# Yet-Another-LED-Cube.net
KiCad netlist of a schematic drawn in EAGLE
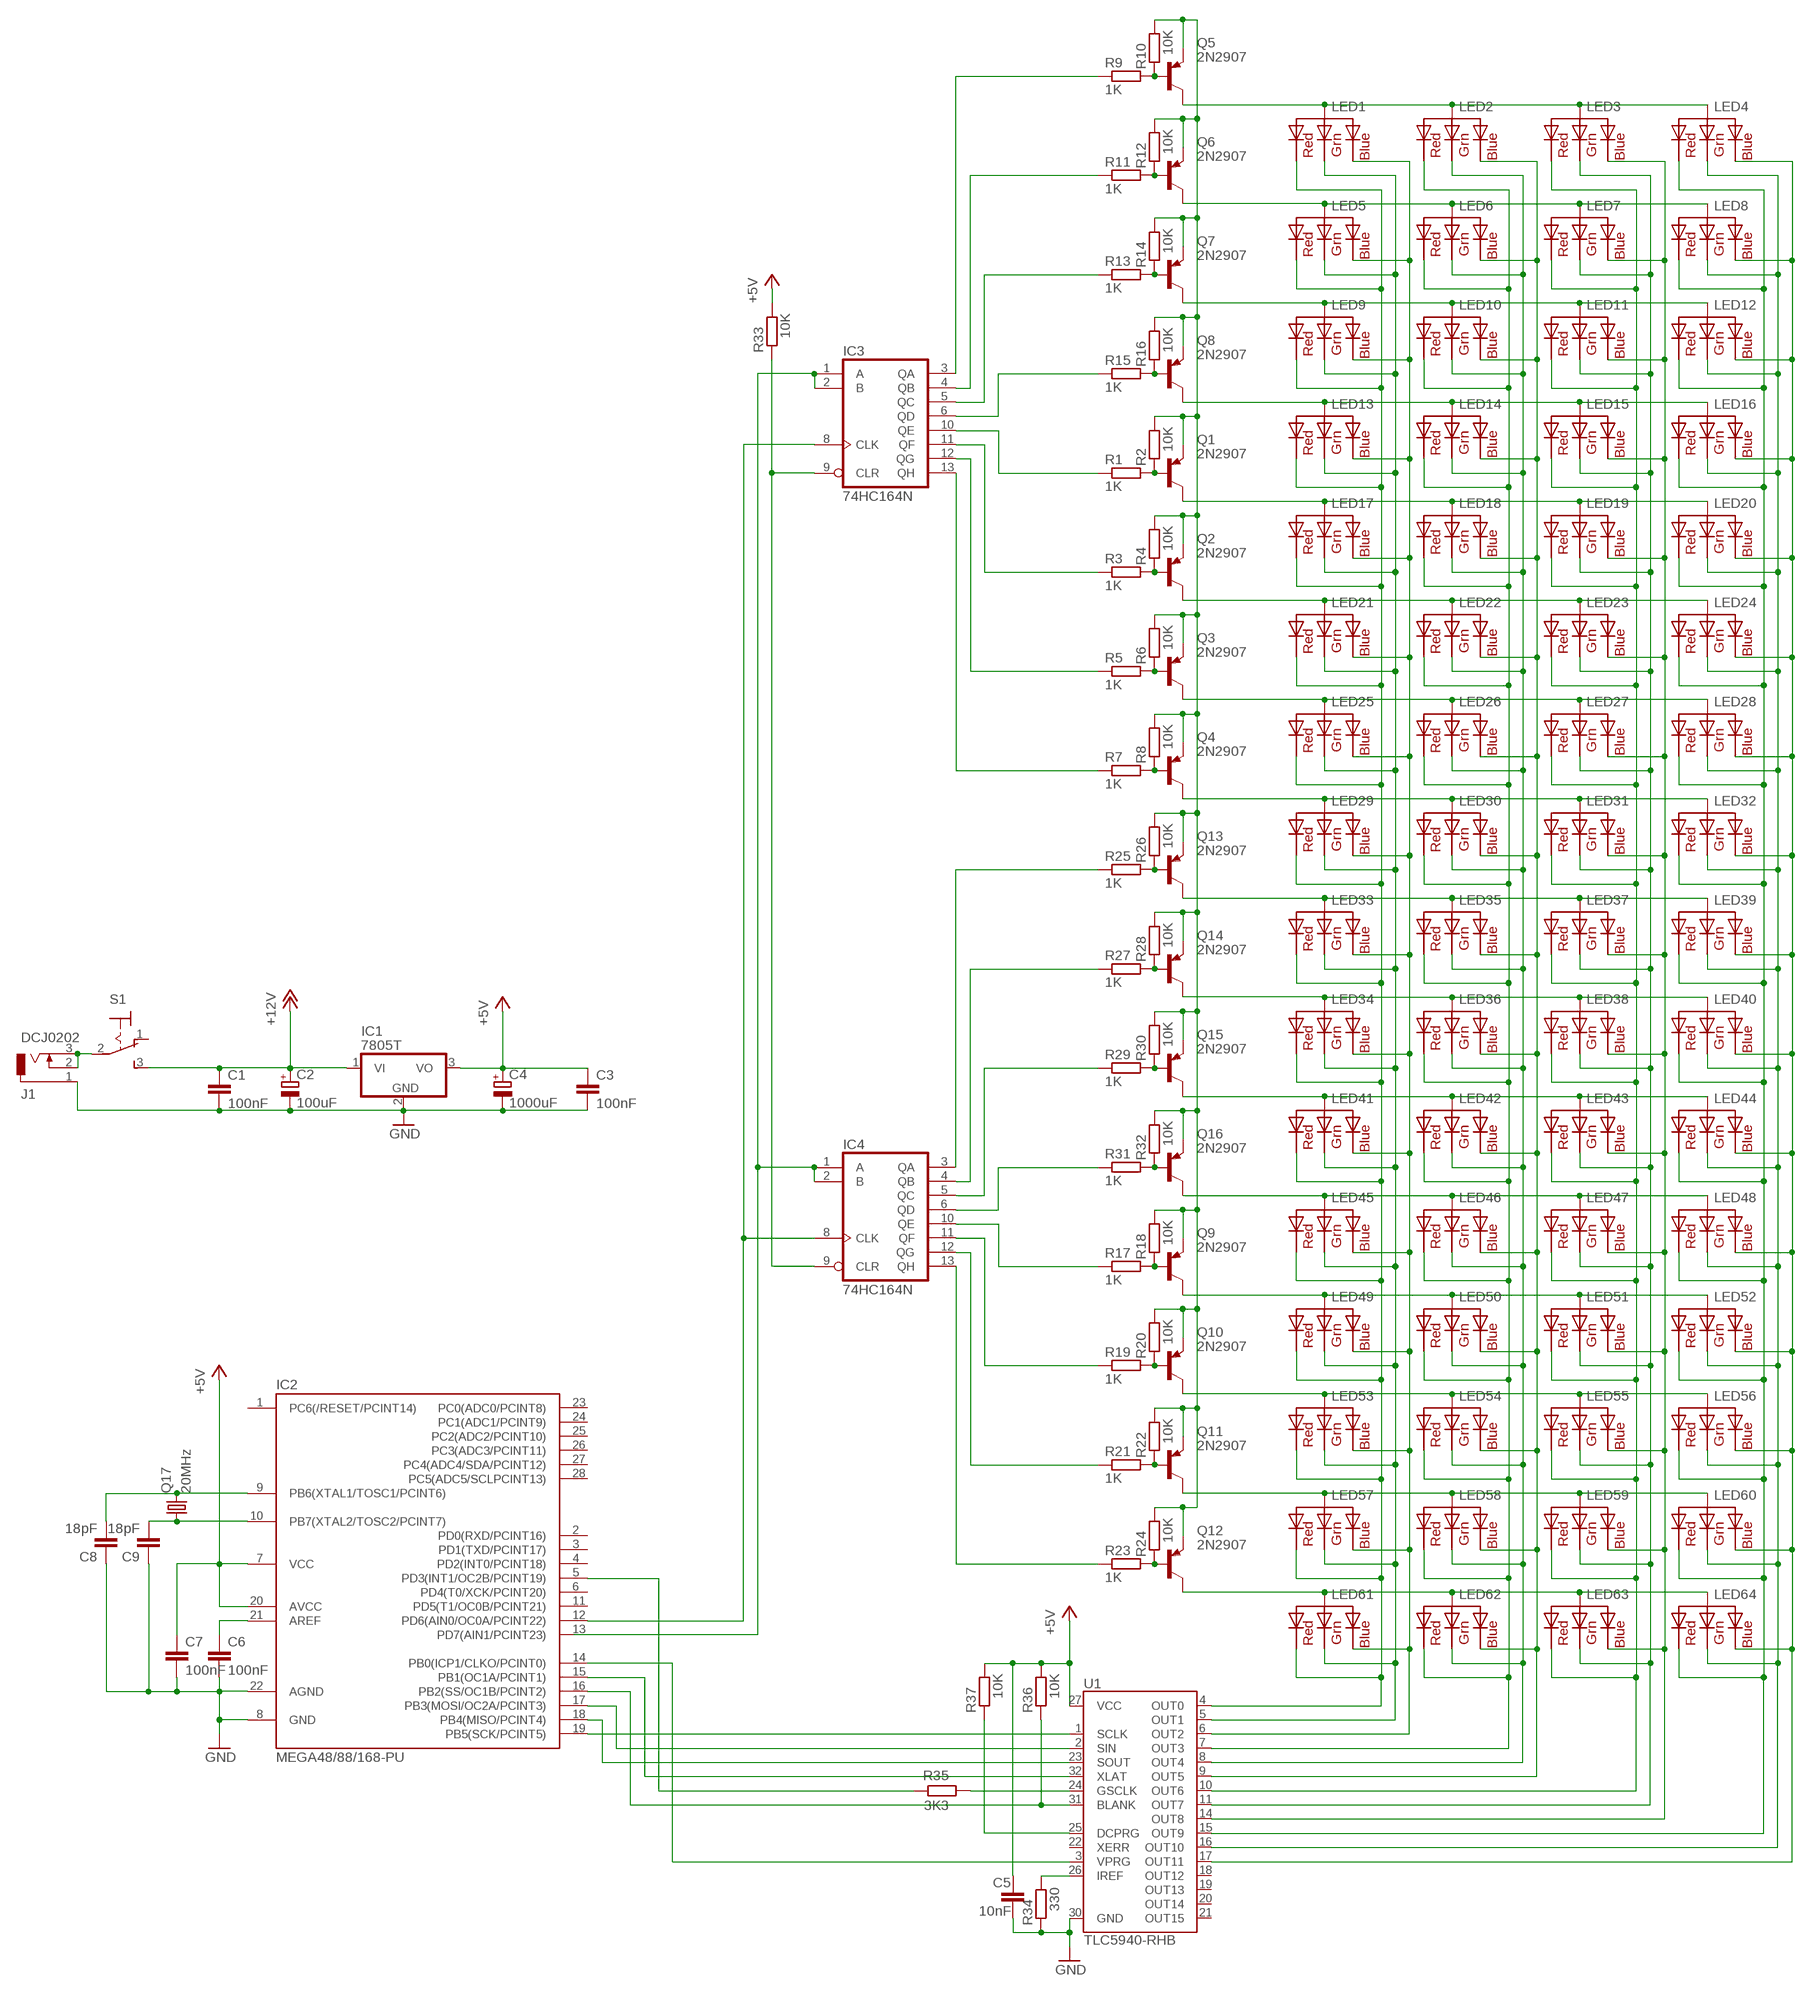
[diagram p0: schematic, sheet 1]

(export (version "E")
  (design (tool "Eeschema 10.0.6"))
  (components
    (comp (ref "C1")
      (value "100nF")
      (footprint "eagle-import:C025-024X044")
      (libsource (lib "eagle-import") (part "C-EU025-024X044"))
    )
    (comp (ref "C2")
      (value "100uF")
      (footprint "eagle-import:E2,5-7")
      (libsource (lib "eagle-import") (part "CPOL-EUE2.5-7"))
    )
    (comp (ref "C3")
      (value "100nF")
      (footprint "eagle-import:C025-024X044")
      (libsource (lib "eagle-import") (part "C-EU025-024X044"))
    )
    (comp (ref "C4")
      (value "1000uF")
      (footprint "eagle-import:E3,5-10")
      (libsource (lib "eagle-import") (part "CPOL-EUE3.5-10"))
    )
    (comp (ref "C5")
      (value "10nF")
      (footprint "eagle-import:C025-024X044")
      (libsource (lib "eagle-import") (part "C-EU025-024X044"))
    )
    (comp (ref "C6")
      (value "100nF")
      (footprint "eagle-import:C025-024X044")
      (libsource (lib "eagle-import") (part "C-EU025-024X044"))
    )
    (comp (ref "C7")
      (value "100nF")
      (footprint "eagle-import:C025-024X044")
      (libsource (lib "eagle-import") (part "C-EU025-024X044"))
    )
    (comp (ref "C8")
      (value "18pF")
      (footprint "eagle-import:C025-024X044")
      (libsource (lib "eagle-import") (part "C-EU025-024X044"))
    )
    (comp (ref "C9")
      (value "18pF")
      (footprint "eagle-import:C025-024X044")
      (libsource (lib "eagle-import") (part "C-EU025-024X044"))
    )
    (comp (ref "IC1")
      (value "7805T")
      (footprint "eagle-import:TO220H")
      (libsource (lib "eagle-import") (part "78T05"))
    )
    (comp (ref "IC2")
      (value "MEGA48/88/168-PU")
      (footprint "eagle-import:DIL28-3")
      (libsource (lib "eagle-import") (part "MEGA48/88/168-PU"))
    )
    (comp (ref "IC3")
      (value "74HC164N")
      (footprint "eagle-import:DIL14")
      (libsource (lib "eagle-import") (part "74164NHC"))
    )
    (comp (ref "IC4")
      (value "74HC164N")
      (footprint "eagle-import:DIL14")
      (libsource (lib "eagle-import") (part "74164NHC"))
    )
    (comp (ref "J1")
      (value "DCJ0202")
      (footprint "eagle-import:DCJ0202")
      (libsource (lib "eagle-import") (part "DCJ0202"))
    )
    (comp (ref "LED1")
      (value "RGBLED_CAA")
      (footprint "eagle-import:LED5MMRGB2")
      (libsource (lib "eagle-import") (part "RGBLED_CAA"))
    )
    (comp (ref "LED2")
      (value "RGBLED_CAA")
      (footprint "eagle-import:LED5MMRGB2")
      (libsource (lib "eagle-import") (part "RGBLED_CAA"))
    )
    (comp (ref "LED3")
      (value "RGBLED_CAA")
      (footprint "eagle-import:LED5MMRGB2")
      (libsource (lib "eagle-import") (part "RGBLED_CAA"))
    )
    (comp (ref "LED4")
      (value "RGBLED_CAA")
      (footprint "eagle-import:LED5MMRGB2")
      (libsource (lib "eagle-import") (part "RGBLED_CAA"))
    )
    (comp (ref "LED5")
      (value "RGBLED_CAA")
      (footprint "eagle-import:LED5MMRGB2")
      (libsource (lib "eagle-import") (part "RGBLED_CAA"))
    )
    (comp (ref "LED6")
      (value "RGBLED_CAA")
      (footprint "eagle-import:LED5MMRGB2")
      (libsource (lib "eagle-import") (part "RGBLED_CAA"))
    )
    (comp (ref "LED7")
      (value "RGBLED_CAA")
      (footprint "eagle-import:LED5MMRGB2")
      (libsource (lib "eagle-import") (part "RGBLED_CAA"))
    )
    (comp (ref "LED8")
      (value "RGBLED_CAA")
      (footprint "eagle-import:LED5MMRGB2")
      (libsource (lib "eagle-import") (part "RGBLED_CAA"))
    )
    (comp (ref "LED9")
      (value "RGBLED_CAA")
      (footprint "eagle-import:LED5MMRGB2")
      (libsource (lib "eagle-import") (part "RGBLED_CAA"))
    )
    (comp (ref "LED10")
      (value "RGBLED_CAA")
      (footprint "eagle-import:LED5MMRGB2")
      (libsource (lib "eagle-import") (part "RGBLED_CAA"))
    )
    (comp (ref "LED11")
      (value "RGBLED_CAA")
      (footprint "eagle-import:LED5MMRGB2")
      (libsource (lib "eagle-import") (part "RGBLED_CAA"))
    )
    (comp (ref "LED12")
      (value "RGBLED_CAA")
      (footprint "eagle-import:LED5MMRGB2")
      (libsource (lib "eagle-import") (part "RGBLED_CAA"))
    )
    (comp (ref "LED13")
      (value "RGBLED_CAA")
      (footprint "eagle-import:LED5MMRGB2")
      (libsource (lib "eagle-import") (part "RGBLED_CAA"))
    )
    (comp (ref "LED14")
      (value "RGBLED_CAA")
      (footprint "eagle-import:LED5MMRGB2")
      (libsource (lib "eagle-import") (part "RGBLED_CAA"))
    )
    (comp (ref "LED15")
      (value "RGBLED_CAA")
      (footprint "eagle-import:LED5MMRGB2")
      (libsource (lib "eagle-import") (part "RGBLED_CAA"))
    )
    (comp (ref "LED16")
      (value "RGBLED_CAA")
      (footprint "eagle-import:LED5MMRGB2")
      (libsource (lib "eagle-import") (part "RGBLED_CAA"))
    )
    (comp (ref "LED17")
      (value "RGBLED_CAA")
      (footprint "eagle-import:LED5MMRGB2")
      (libsource (lib "eagle-import") (part "RGBLED_CAA"))
    )
    (comp (ref "LED18")
      (value "RGBLED_CAA")
      (footprint "eagle-import:LED5MMRGB2")
      (libsource (lib "eagle-import") (part "RGBLED_CAA"))
    )
    (comp (ref "LED19")
      (value "RGBLED_CAA")
      (footprint "eagle-import:LED5MMRGB2")
      (libsource (lib "eagle-import") (part "RGBLED_CAA"))
    )
    (comp (ref "LED20")
      (value "RGBLED_CAA")
      (footprint "eagle-import:LED5MMRGB2")
      (libsource (lib "eagle-import") (part "RGBLED_CAA"))
    )
    (comp (ref "LED21")
      (value "RGBLED_CAA")
      (footprint "eagle-import:LED5MMRGB2")
      (libsource (lib "eagle-import") (part "RGBLED_CAA"))
    )
    (comp (ref "LED22")
      (value "RGBLED_CAA")
      (footprint "eagle-import:LED5MMRGB2")
      (libsource (lib "eagle-import") (part "RGBLED_CAA"))
    )
    (comp (ref "LED23")
      (value "RGBLED_CAA")
      (footprint "eagle-import:LED5MMRGB2")
      (libsource (lib "eagle-import") (part "RGBLED_CAA"))
    )
    (comp (ref "LED24")
      (value "RGBLED_CAA")
      (footprint "eagle-import:LED5MMRGB2")
      (libsource (lib "eagle-import") (part "RGBLED_CAA"))
    )
    (comp (ref "LED25")
      (value "RGBLED_CAA")
      (footprint "eagle-import:LED5MMRGB2")
      (libsource (lib "eagle-import") (part "RGBLED_CAA"))
    )
    (comp (ref "LED26")
      (value "RGBLED_CAA")
      (footprint "eagle-import:LED5MMRGB2")
      (libsource (lib "eagle-import") (part "RGBLED_CAA"))
    )
    (comp (ref "LED27")
      (value "RGBLED_CAA")
      (footprint "eagle-import:LED5MMRGB2")
      (libsource (lib "eagle-import") (part "RGBLED_CAA"))
    )
    (comp (ref "LED28")
      (value "RGBLED_CAA")
      (footprint "eagle-import:LED5MMRGB2")
      (libsource (lib "eagle-import") (part "RGBLED_CAA"))
    )
    (comp (ref "LED29")
      (value "RGBLED_CAA")
      (footprint "eagle-import:LED5MMRGB2")
      (libsource (lib "eagle-import") (part "RGBLED_CAA"))
    )
    (comp (ref "LED30")
      (value "RGBLED_CAA")
      (footprint "eagle-import:LED5MMRGB2")
      (libsource (lib "eagle-import") (part "RGBLED_CAA"))
    )
    (comp (ref "LED31")
      (value "RGBLED_CAA")
      (footprint "eagle-import:LED5MMRGB2")
      (libsource (lib "eagle-import") (part "RGBLED_CAA"))
    )
    (comp (ref "LED32")
      (value "RGBLED_CAA")
      (footprint "eagle-import:LED5MMRGB2")
      (libsource (lib "eagle-import") (part "RGBLED_CAA"))
    )
    (comp (ref "LED33")
      (value "RGBLED_CAA")
      (footprint "eagle-import:LED5MMRGB2")
      (libsource (lib "eagle-import") (part "RGBLED_CAA"))
    )
    (comp (ref "LED34")
      (value "RGBLED_CAA")
      (footprint "eagle-import:LED5MMRGB2")
      (libsource (lib "eagle-import") (part "RGBLED_CAA"))
    )
    (comp (ref "LED35")
      (value "RGBLED_CAA")
      (footprint "eagle-import:LED5MMRGB2")
      (libsource (lib "eagle-import") (part "RGBLED_CAA"))
    )
    (comp (ref "LED36")
      (value "RGBLED_CAA")
      (footprint "eagle-import:LED5MMRGB2")
      (libsource (lib "eagle-import") (part "RGBLED_CAA"))
    )
    (comp (ref "LED37")
      (value "RGBLED_CAA")
      (footprint "eagle-import:LED5MMRGB2")
      (libsource (lib "eagle-import") (part "RGBLED_CAA"))
    )
    (comp (ref "LED38")
      (value "RGBLED_CAA")
      (footprint "eagle-import:LED5MMRGB2")
      (libsource (lib "eagle-import") (part "RGBLED_CAA"))
    )
    (comp (ref "LED39")
      (value "RGBLED_CAA")
      (footprint "eagle-import:LED5MMRGB2")
      (libsource (lib "eagle-import") (part "RGBLED_CAA"))
    )
    (comp (ref "LED40")
      (value "RGBLED_CAA")
      (footprint "eagle-import:LED5MMRGB2")
      (libsource (lib "eagle-import") (part "RGBLED_CAA"))
    )
    (comp (ref "LED41")
      (value "RGBLED_CAA")
      (footprint "eagle-import:LED5MMRGB2")
      (libsource (lib "eagle-import") (part "RGBLED_CAA"))
    )
    (comp (ref "LED42")
      (value "RGBLED_CAA")
      (footprint "eagle-import:LED5MMRGB2")
      (libsource (lib "eagle-import") (part "RGBLED_CAA"))
    )
    (comp (ref "LED43")
      (value "RGBLED_CAA")
      (footprint "eagle-import:LED5MMRGB2")
      (libsource (lib "eagle-import") (part "RGBLED_CAA"))
    )
    (comp (ref "LED44")
      (value "RGBLED_CAA")
      (footprint "eagle-import:LED5MMRGB2")
      (libsource (lib "eagle-import") (part "RGBLED_CAA"))
    )
    (comp (ref "LED45")
      (value "RGBLED_CAA")
      (footprint "eagle-import:LED5MMRGB2")
      (libsource (lib "eagle-import") (part "RGBLED_CAA"))
    )
    (comp (ref "LED46")
      (value "RGBLED_CAA")
      (footprint "eagle-import:LED5MMRGB2")
      (libsource (lib "eagle-import") (part "RGBLED_CAA"))
    )
    (comp (ref "LED47")
      (value "RGBLED_CAA")
      (footprint "eagle-import:LED5MMRGB2")
      (libsource (lib "eagle-import") (part "RGBLED_CAA"))
    )
    (comp (ref "LED48")
      (value "RGBLED_CAA")
      (footprint "eagle-import:LED5MMRGB2")
      (libsource (lib "eagle-import") (part "RGBLED_CAA"))
    )
    (comp (ref "LED49")
      (value "RGBLED_CAA")
      (footprint "eagle-import:LED5MMRGB2")
      (libsource (lib "eagle-import") (part "RGBLED_CAA"))
    )
    (comp (ref "LED50")
      (value "RGBLED_CAA")
      (footprint "eagle-import:LED5MMRGB2")
      (libsource (lib "eagle-import") (part "RGBLED_CAA"))
    )
    (comp (ref "LED51")
      (value "RGBLED_CAA")
      (footprint "eagle-import:LED5MMRGB2")
      (libsource (lib "eagle-import") (part "RGBLED_CAA"))
    )
    (comp (ref "LED52")
      (value "RGBLED_CAA")
      (footprint "eagle-import:LED5MMRGB2")
      (libsource (lib "eagle-import") (part "RGBLED_CAA"))
    )
    (comp (ref "LED53")
      (value "RGBLED_CAA")
      (footprint "eagle-import:LED5MMRGB2")
      (libsource (lib "eagle-import") (part "RGBLED_CAA"))
    )
    (comp (ref "LED54")
      (value "RGBLED_CAA")
      (footprint "eagle-import:LED5MMRGB2")
      (libsource (lib "eagle-import") (part "RGBLED_CAA"))
    )
    (comp (ref "LED55")
      (value "RGBLED_CAA")
      (footprint "eagle-import:LED5MMRGB2")
      (libsource (lib "eagle-import") (part "RGBLED_CAA"))
    )
    (comp (ref "LED56")
      (value "RGBLED_CAA")
      (footprint "eagle-import:LED5MMRGB2")
      (libsource (lib "eagle-import") (part "RGBLED_CAA"))
    )
    (comp (ref "LED57")
      (value "RGBLED_CAA")
      (footprint "eagle-import:LED5MMRGB2")
      (libsource (lib "eagle-import") (part "RGBLED_CAA"))
    )
    (comp (ref "LED58")
      (value "RGBLED_CAA")
      (footprint "eagle-import:LED5MMRGB2")
      (libsource (lib "eagle-import") (part "RGBLED_CAA"))
    )
    (comp (ref "LED59")
      (value "RGBLED_CAA")
      (footprint "eagle-import:LED5MMRGB2")
      (libsource (lib "eagle-import") (part "RGBLED_CAA"))
    )
    (comp (ref "LED60")
      (value "RGBLED_CAA")
      (footprint "eagle-import:LED5MMRGB2")
      (libsource (lib "eagle-import") (part "RGBLED_CAA"))
    )
    (comp (ref "LED61")
      (value "RGBLED_CAA")
      (footprint "eagle-import:LED5MMRGB2")
      (libsource (lib "eagle-import") (part "RGBLED_CAA"))
    )
    (comp (ref "LED62")
      (value "RGBLED_CAA")
      (footprint "eagle-import:LED5MMRGB2")
      (libsource (lib "eagle-import") (part "RGBLED_CAA"))
    )
    (comp (ref "LED63")
      (value "RGBLED_CAA")
      (footprint "eagle-import:LED5MMRGB2")
      (libsource (lib "eagle-import") (part "RGBLED_CAA"))
    )
    (comp (ref "LED64")
      (value "RGBLED_CAA")
      (footprint "eagle-import:LED5MMRGB2")
      (libsource (lib "eagle-import") (part "RGBLED_CAA"))
    )
    (comp (ref "Q1")
      (value "2N2907")
      (footprint "eagle-import:TO18")
      (libsource (lib "eagle-import") (part "2N2907"))
    )
    (comp (ref "Q2")
      (value "2N2907")
      (footprint "eagle-import:TO18")
      (libsource (lib "eagle-import") (part "2N2907"))
    )
    (comp (ref "Q3")
      (value "2N2907")
      (footprint "eagle-import:TO18")
      (libsource (lib "eagle-import") (part "2N2907"))
    )
    (comp (ref "Q4")
      (value "2N2907")
      (footprint "eagle-import:TO18")
      (libsource (lib "eagle-import") (part "2N2907"))
    )
    (comp (ref "Q5")
      (value "2N2907")
      (footprint "eagle-import:TO18")
      (libsource (lib "eagle-import") (part "2N2907"))
    )
    (comp (ref "Q6")
      (value "2N2907")
      (footprint "eagle-import:TO18")
      (libsource (lib "eagle-import") (part "2N2907"))
    )
    (comp (ref "Q7")
      (value "2N2907")
      (footprint "eagle-import:TO18")
      (libsource (lib "eagle-import") (part "2N2907"))
    )
    (comp (ref "Q8")
      (value "2N2907")
      (footprint "eagle-import:TO18")
      (libsource (lib "eagle-import") (part "2N2907"))
    )
    (comp (ref "Q9")
      (value "2N2907")
      (footprint "eagle-import:TO18")
      (libsource (lib "eagle-import") (part "2N2907"))
    )
    (comp (ref "Q10")
      (value "2N2907")
      (footprint "eagle-import:TO18")
      (libsource (lib "eagle-import") (part "2N2907"))
    )
    (comp (ref "Q11")
      (value "2N2907")
      (footprint "eagle-import:TO18")
      (libsource (lib "eagle-import") (part "2N2907"))
    )
    (comp (ref "Q12")
      (value "2N2907")
      (footprint "eagle-import:TO18")
      (libsource (lib "eagle-import") (part "2N2907"))
    )
    (comp (ref "Q13")
      (value "2N2907")
      (footprint "eagle-import:TO18")
      (libsource (lib "eagle-import") (part "2N2907"))
    )
    (comp (ref "Q14")
      (value "2N2907")
      (footprint "eagle-import:TO18")
      (libsource (lib "eagle-import") (part "2N2907"))
    )
    (comp (ref "Q15")
      (value "2N2907")
      (footprint "eagle-import:TO18")
      (libsource (lib "eagle-import") (part "2N2907"))
    )
    (comp (ref "Q16")
      (value "2N2907")
      (footprint "eagle-import:TO18")
      (libsource (lib "eagle-import") (part "2N2907"))
    )
    (comp (ref "Q17")
      (value "20MHz")
      (footprint "eagle-import:HC49_S")
      (libsource (lib "eagle-import") (part "CRYSTALHC49S"))
    )
    (comp (ref "R1")
      (value "1K")
      (footprint "eagle-import:0204V")
      (libsource (lib "eagle-import") (part "R-EU_0204/2V"))
    )
    (comp (ref "R2")
      (value "10K")
      (footprint "eagle-import:0204V")
      (libsource (lib "eagle-import") (part "R-EU_0204/2V"))
    )
    (comp (ref "R3")
      (value "1K")
      (footprint "eagle-import:0204V")
      (libsource (lib "eagle-import") (part "R-EU_0204/2V"))
    )
    (comp (ref "R4")
      (value "10K")
      (footprint "eagle-import:0204V")
      (libsource (lib "eagle-import") (part "R-EU_0204/2V"))
    )
    (comp (ref "R5")
      (value "1K")
      (footprint "eagle-import:0204V")
      (libsource (lib "eagle-import") (part "R-EU_0204/2V"))
    )
    (comp (ref "R6")
      (value "10K")
      (footprint "eagle-import:0204V")
      (libsource (lib "eagle-import") (part "R-EU_0204/2V"))
    )
    (comp (ref "R7")
      (value "1K")
      (footprint "eagle-import:0204V")
      (libsource (lib "eagle-import") (part "R-EU_0204/2V"))
    )
    (comp (ref "R8")
      (value "10K")
      (footprint "eagle-import:0204V")
      (libsource (lib "eagle-import") (part "R-EU_0204/2V"))
    )
    (comp (ref "R9")
      (value "1K")
      (footprint "eagle-import:0204V")
      (libsource (lib "eagle-import") (part "R-EU_0204/2V"))
    )
    (comp (ref "R10")
      (value "10K")
      (footprint "eagle-import:0204V")
      (libsource (lib "eagle-import") (part "R-EU_0204/2V"))
    )
    (comp (ref "R11")
      (value "1K")
      (footprint "eagle-import:0204V")
      (libsource (lib "eagle-import") (part "R-EU_0204/2V"))
    )
    (comp (ref "R12")
      (value "10K")
      (footprint "eagle-import:0204V")
      (libsource (lib "eagle-import") (part "R-EU_0204/2V"))
    )
    (comp (ref "R13")
      (value "1K")
      (footprint "eagle-import:0204V")
      (libsource (lib "eagle-import") (part "R-EU_0204/2V"))
    )
    (comp (ref "R14")
      (value "10K")
      (footprint "eagle-import:0204V")
      (libsource (lib "eagle-import") (part "R-EU_0204/2V"))
    )
    (comp (ref "R15")
      (value "1K")
      (footprint "eagle-import:0204V")
      (libsource (lib "eagle-import") (part "R-EU_0204/2V"))
    )
    (comp (ref "R16")
      (value "10K")
      (footprint "eagle-import:0204V")
      (libsource (lib "eagle-import") (part "R-EU_0204/2V"))
    )
    (comp (ref "R17")
      (value "1K")
      (footprint "eagle-import:0204V")
      (libsource (lib "eagle-import") (part "R-EU_0204/2V"))
    )
    (comp (ref "R18")
      (value "10K")
      (footprint "eagle-import:0204V")
      (libsource (lib "eagle-import") (part "R-EU_0204/2V"))
    )
    (comp (ref "R19")
      (value "1K")
      (footprint "eagle-import:0204V")
      (libsource (lib "eagle-import") (part "R-EU_0204/2V"))
    )
    (comp (ref "R20")
      (value "10K")
      (footprint "eagle-import:0204V")
      (libsource (lib "eagle-import") (part "R-EU_0204/2V"))
    )
    (comp (ref "R21")
      (value "1K")
      (footprint "eagle-import:0204V")
      (libsource (lib "eagle-import") (part "R-EU_0204/2V"))
    )
    (comp (ref "R22")
      (value "10K")
      (footprint "eagle-import:0204V")
      (libsource (lib "eagle-import") (part "R-EU_0204/2V"))
    )
    (comp (ref "R23")
      (value "1K")
      (footprint "eagle-import:0204V")
      (libsource (lib "eagle-import") (part "R-EU_0204/2V"))
    )
    (comp (ref "R24")
      (value "10K")
      (footprint "eagle-import:0204V")
      (libsource (lib "eagle-import") (part "R-EU_0204/2V"))
    )
    (comp (ref "R25")
      (value "1K")
      (footprint "eagle-import:0204V")
      (libsource (lib "eagle-import") (part "R-EU_0204/2V"))
    )
    (comp (ref "R26")
      (value "10K")
      (footprint "eagle-import:0204V")
      (libsource (lib "eagle-import") (part "R-EU_0204/2V"))
    )
    (comp (ref "R27")
      (value "1K")
      (footprint "eagle-import:0204V")
      (libsource (lib "eagle-import") (part "R-EU_0204/2V"))
    )
    (comp (ref "R28")
      (value "10K")
      (footprint "eagle-import:0204V")
      (libsource (lib "eagle-import") (part "R-EU_0204/2V"))
    )
    (comp (ref "R29")
      (value "1K")
      (footprint "eagle-import:0204V")
      (libsource (lib "eagle-import") (part "R-EU_0204/2V"))
    )
    (comp (ref "R30")
      (value "10K")
      (footprint "eagle-import:0204V")
      (libsource (lib "eagle-import") (part "R-EU_0204/2V"))
    )
    (comp (ref "R31")
      (value "1K")
      (footprint "eagle-import:0204V")
      (libsource (lib "eagle-import") (part "R-EU_0204/2V"))
    )
    (comp (ref "R32")
      (value "10K")
      (footprint "eagle-import:0204V")
      (libsource (lib "eagle-import") (part "R-EU_0204/2V"))
    )
    (comp (ref "R33")
      (value "10K")
      (footprint "eagle-import:0204V")
      (libsource (lib "eagle-import") (part "R-EU_0204/2V"))
    )
    (comp (ref "R34")
      (value "330")
      (footprint "eagle-import:0204V")
      (libsource (lib "eagle-import") (part "R-EU_0204/2V"))
    )
    (comp (ref "R35")
      (value "3K3")
      (footprint "eagle-import:0204V")
      (libsource (lib "eagle-import") (part "R-EU_0204/2V"))
    )
    (comp (ref "R36")
      (value "10K")
      (footprint "eagle-import:0204V")
      (libsource (lib "eagle-import") (part "R-EU_0204/2V"))
    )
    (comp (ref "R37")
      (value "10K")
      (footprint "eagle-import:0204V")
      (libsource (lib "eagle-import") (part "R-EU_0204/2V"))
    )
    (comp (ref "S1")
      (value "320-916")
      (footprint "eagle-import:320-916")
      (libsource (lib "eagle-import") (part "320-916"))
    )
    (comp (ref "U1")
      (value "TLC5940-RHB")
      (footprint "eagle-import:QFN-32")
      (libsource (lib "eagle-import") (part "TLC5940-RHB"))
    )
  )
  (nets
    (net (code "1") (name "+5V") (class "Default")
      (node (ref "C3") (pin "1") (pinfunction "1_1") (pintype "passive"))
      (node (ref "C4") (pin "+") (pinfunction "+_+") (pintype "passive"))
      (node (ref "C5") (pin "1") (pinfunction "1_1") (pintype "passive"))
      (node (ref "C7") (pin "1") (pinfunction "1_1") (pintype "passive"))
      (node (ref "IC1") (pin "3") (pinfunction "VO_3") (pintype "passive"))
      (node (ref "IC2") (pin "20") (pinfunction "AVCC_20") (pintype "passive"))
      (node (ref "IC2") (pin "7") (pinfunction "VCC_7") (pintype "power_in"))
      (node (ref "R33") (pin "2") (pinfunction "2_2") (pintype "passive"))
      (node (ref "R36") (pin "2") (pinfunction "2_2") (pintype "passive"))
      (node (ref "R37") (pin "2") (pinfunction "2_2") (pintype "passive"))
      (node (ref "U1") (pin "27") (pinfunction "VCC_27") (pintype "bidirectional"))
    )
    (net (code "2") (name "+12V") (class "Default")
      (node (ref "C1") (pin "1") (pinfunction "1_1") (pintype "passive"))
      (node (ref "C2") (pin "+") (pinfunction "+_+") (pintype "passive"))
      (node (ref "IC1") (pin "1") (pinfunction "VI_1") (pintype "input"))
      (node (ref "S1") (pin "3") (pinfunction "S_3") (pintype "passive"))
    )
    (net (code "3") (name "GND") (class "Default")
      (node (ref "C1") (pin "2") (pinfunction "2_2") (pintype "passive"))
      (node (ref "C2") (pin "-") (pinfunction "-_-") (pintype "passive"))
      (node (ref "C3") (pin "2") (pinfunction "2_2") (pintype "passive"))
      (node (ref "C4") (pin "-") (pinfunction "-_-") (pintype "passive"))
      (node (ref "C5") (pin "2") (pinfunction "2_2") (pintype "passive"))
      (node (ref "C6") (pin "2") (pinfunction "2_2") (pintype "passive"))
      (node (ref "C7") (pin "2") (pinfunction "2_2") (pintype "passive"))
      (node (ref "C8") (pin "1") (pinfunction "1_1") (pintype "passive"))
      (node (ref "C9") (pin "1") (pinfunction "1_1") (pintype "passive"))
      (node (ref "IC1") (pin "2") (pinfunction "GND_2") (pintype "passive"))
      (node (ref "IC2") (pin "22") (pinfunction "AGND_22") (pintype "power_in"))
      (node (ref "IC2") (pin "8") (pinfunction "GND_8") (pintype "power_in"))
      (node (ref "J1") (pin "1") (pinfunction "1_1") (pintype "passive"))
      (node (ref "R34") (pin "1") (pinfunction "1_1") (pintype "passive"))
      (node (ref "U1") (pin "30") (pinfunction "GND_30") (pintype "bidirectional"))
    )
    (net (code "4") (name "Net-(IC2-AREF)") (class "Default")
      (node (ref "C6") (pin "1") (pinfunction "1_1") (pintype "passive"))
      (node (ref "IC2") (pin "21") (pinfunction "AREF_21") (pintype "passive"))
    )
    (net (code "5") (name "Net-(IC2-PB0(ICP1{slash}CLKO{slash}PCINT0))") (class "Default")
      (node (ref "IC2") (pin "14") (pinfunction "PB0(ICP1/CLKO/PCINT0)_14") (pintype "bidirectional"))
      (node (ref "U1") (pin "3") (pinfunction "VPRG_3") (pintype "bidirectional"))
    )
    (net (code "6") (name "Net-(IC2-PB1(OC1A{slash}PCINT1))") (class "Default")
      (node (ref "IC2") (pin "15") (pinfunction "PB1(OC1A/PCINT1)_15") (pintype "bidirectional"))
      (node (ref "U1") (pin "32") (pinfunction "XLAT_32") (pintype "bidirectional"))
    )
    (net (code "7") (name "Net-(IC2-PB2(SS{slash}OC1B{slash}PCINT2))") (class "Default")
      (node (ref "IC2") (pin "16") (pinfunction "PB2(SS/OC1B/PCINT2)_16") (pintype "bidirectional"))
      (node (ref "R36") (pin "1") (pinfunction "1_1") (pintype "passive"))
      (node (ref "U1") (pin "31") (pinfunction "BLANK_31") (pintype "bidirectional"))
    )
    (net (code "8") (name "Net-(IC2-PB3(MOSI{slash}OC2A{slash}PCINT3))") (class "Default")
      (node (ref "IC2") (pin "17") (pinfunction "PB3(MOSI/OC2A/PCINT3)_17") (pintype "bidirectional"))
      (node (ref "U1") (pin "2") (pinfunction "SIN_2") (pintype "bidirectional"))
    )
    (net (code "9") (name "Net-(IC2-PB4(MISO{slash}PCINT4))") (class "Default")
      (node (ref "IC2") (pin "18") (pinfunction "PB4(MISO/PCINT4)_18") (pintype "bidirectional"))
      (node (ref "U1") (pin "23") (pinfunction "SOUT_23") (pintype "bidirectional"))
    )
    (net (code "10") (name "Net-(IC2-PB5(SCK{slash}PCINT5))") (class "Default")
      (node (ref "IC2") (pin "19") (pinfunction "PB5(SCK/PCINT5)_19") (pintype "bidirectional"))
      (node (ref "U1") (pin "1") (pinfunction "SCLK_1") (pintype "bidirectional"))
    )
    (net (code "11") (name "Net-(IC2-PB6(XTAL1{slash}TOSC1{slash}PCINT6))") (class "Default")
      (node (ref "C8") (pin "2") (pinfunction "2_2") (pintype "passive"))
      (node (ref "IC2") (pin "9") (pinfunction "PB6(XTAL1/TOSC1/PCINT6)_9") (pintype "bidirectional"))
      (node (ref "Q17") (pin "2") (pinfunction "2_2") (pintype "passive"))
    )
    (net (code "12") (name "Net-(IC2-PB7(XTAL2{slash}TOSC2{slash}PCINT7))") (class "Default")
      (node (ref "C9") (pin "2") (pinfunction "2_2") (pintype "passive"))
      (node (ref "IC2") (pin "10") (pinfunction "PB7(XTAL2/TOSC2/PCINT7)_10") (pintype "bidirectional"))
      (node (ref "Q17") (pin "1") (pinfunction "1_1") (pintype "passive"))
    )
    (net (code "13") (name "Net-(IC2-PD3(INT1{slash}OC2B{slash}PCINT19))") (class "Default")
      (node (ref "IC2") (pin "5") (pinfunction "PD3(INT1/OC2B/PCINT19)_5") (pintype "bidirectional"))
      (node (ref "R35") (pin "2") (pinfunction "2_2") (pintype "passive"))
    )
    (net (code "14") (name "Net-(IC2-PD6(AIN0{slash}OC0A{slash}PCINT22))") (class "Default")
      (node (ref "IC2") (pin "12") (pinfunction "PD6(AIN0/OC0A/PCINT22)_12") (pintype "bidirectional"))
      (node (ref "IC3") (pin "8") (pinfunction "CLK_8") (pintype "input"))
      (node (ref "IC4") (pin "8") (pinfunction "CLK_8") (pintype "input"))
    )
    (net (code "15") (name "Net-(IC3A-A)") (class "Default")
      (node (ref "IC3") (pin "1") (pinfunction "A_1") (pintype "input"))
      (node (ref "IC3") (pin "2") (pinfunction "B_2") (pintype "input"))
      (node (ref "IC4") (pin "1") (pinfunction "A_1") (pintype "input"))
      (node (ref "IC4") (pin "2") (pinfunction "B_2") (pintype "input"))
    )
    (net (code "16") (name "Net-(IC3A-CLR)") (class "Default")
      (node (ref "IC3") (pin "9") (pinfunction "CLR_9") (pintype "input"))
      (node (ref "IC4") (pin "9") (pinfunction "CLR_9") (pintype "input"))
      (node (ref "R33") (pin "1") (pinfunction "1_1") (pintype "passive"))
    )
    (net (code "17") (name "Net-(IC3A-QA)") (class "Default")
      (node (ref "IC3") (pin "3") (pinfunction "QA_3") (pintype "output"))
      (node (ref "R9") (pin "1") (pinfunction "1_1") (pintype "passive"))
    )
    (net (code "18") (name "Net-(IC3A-QB)") (class "Default")
      (node (ref "IC3") (pin "4") (pinfunction "QB_4") (pintype "output"))
      (node (ref "R11") (pin "1") (pinfunction "1_1") (pintype "passive"))
    )
    (net (code "19") (name "Net-(IC3A-QC)") (class "Default")
      (node (ref "IC3") (pin "5") (pinfunction "QC_5") (pintype "output"))
      (node (ref "R13") (pin "1") (pinfunction "1_1") (pintype "passive"))
    )
    (net (code "20") (name "Net-(IC3A-QD)") (class "Default")
      (node (ref "IC3") (pin "6") (pinfunction "QD_6") (pintype "output"))
      (node (ref "R15") (pin "1") (pinfunction "1_1") (pintype "passive"))
    )
    (net (code "21") (name "Net-(IC3A-QE)") (class "Default")
      (node (ref "IC3") (pin "10") (pinfunction "QE_10") (pintype "output"))
      (node (ref "R1") (pin "1") (pinfunction "1_1") (pintype "passive"))
    )
    (net (code "22") (name "Net-(IC3A-QF)") (class "Default")
      (node (ref "IC3") (pin "11") (pinfunction "QF_11") (pintype "output"))
      (node (ref "R3") (pin "1") (pinfunction "1_1") (pintype "passive"))
    )
    (net (code "23") (name "Net-(IC3A-QG)") (class "Default")
      (node (ref "IC3") (pin "12") (pinfunction "QG_12") (pintype "output"))
      (node (ref "R5") (pin "1") (pinfunction "1_1") (pintype "passive"))
    )
    (net (code "24") (name "Net-(IC3A-QH)") (class "Default")
      (node (ref "IC3") (pin "13") (pinfunction "QH_13") (pintype "output"))
      (node (ref "R7") (pin "1") (pinfunction "1_1") (pintype "passive"))
    )
    (net (code "25") (name "Net-(IC4A-QA)") (class "Default")
      (node (ref "IC4") (pin "3") (pinfunction "QA_3") (pintype "output"))
      (node (ref "R25") (pin "1") (pinfunction "1_1") (pintype "passive"))
    )
    (net (code "26") (name "Net-(IC4A-QB)") (class "Default")
      (node (ref "IC4") (pin "4") (pinfunction "QB_4") (pintype "output"))
      (node (ref "R27") (pin "1") (pinfunction "1_1") (pintype "passive"))
    )
    (net (code "27") (name "Net-(IC4A-QC)") (class "Default")
      (node (ref "IC4") (pin "5") (pinfunction "QC_5") (pintype "output"))
      (node (ref "R29") (pin "1") (pinfunction "1_1") (pintype "passive"))
    )
    (net (code "28") (name "Net-(IC4A-QD)") (class "Default")
      (node (ref "IC4") (pin "6") (pinfunction "QD_6") (pintype "output"))
      (node (ref "R31") (pin "1") (pinfunction "1_1") (pintype "passive"))
    )
    (net (code "29") (name "Net-(IC4A-QE)") (class "Default")
      (node (ref "IC4") (pin "10") (pinfunction "QE_10") (pintype "output"))
      (node (ref "R17") (pin "1") (pinfunction "1_1") (pintype "passive"))
    )
    (net (code "30") (name "Net-(IC4A-QF)") (class "Default")
      (node (ref "IC4") (pin "11") (pinfunction "QF_11") (pintype "output"))
      (node (ref "R19") (pin "1") (pinfunction "1_1") (pintype "passive"))
    )
    (net (code "31") (name "Net-(IC4A-QG)") (class "Default")
      (node (ref "IC4") (pin "12") (pinfunction "QG_12") (pintype "output"))
      (node (ref "R21") (pin "1") (pinfunction "1_1") (pintype "passive"))
    )
    (net (code "32") (name "Net-(IC4A-QH)") (class "Default")
      (node (ref "IC4") (pin "13") (pinfunction "QH_13") (pintype "output"))
      (node (ref "R23") (pin "1") (pinfunction "1_1") (pintype "passive"))
    )
    (net (code "33") (name "Net-(LED1-BLUE)") (class "Default")
      (node (ref "LED1") (pin "P$4") (pinfunction "BLUE_P$4") (pintype "bidirectional"))
      (node (ref "LED13") (pin "P$4") (pinfunction "BLUE_P$4") (pintype "bidirectional"))
      (node (ref "LED17") (pin "P$4") (pinfunction "BLUE_P$4") (pintype "bidirectional"))
      (node (ref "LED21") (pin "P$4") (pinfunction "BLUE_P$4") (pintype "bidirectional"))
      (node (ref "LED25") (pin "P$4") (pinfunction "BLUE_P$4") (pintype "bidirectional"))
      (node (ref "LED29") (pin "P$4") (pinfunction "BLUE_P$4") (pintype "bidirectional"))
      (node (ref "LED33") (pin "P$4") (pinfunction "BLUE_P$4") (pintype "bidirectional"))
      (node (ref "LED34") (pin "P$4") (pinfunction "BLUE_P$4") (pintype "bidirectional"))
      (node (ref "LED41") (pin "P$4") (pinfunction "BLUE_P$4") (pintype "bidirectional"))
      (node (ref "LED45") (pin "P$4") (pinfunction "BLUE_P$4") (pintype "bidirectional"))
      (node (ref "LED49") (pin "P$4") (pinfunction "BLUE_P$4") (pintype "bidirectional"))
      (node (ref "LED5") (pin "P$4") (pinfunction "BLUE_P$4") (pintype "bidirectional"))
      (node (ref "LED53") (pin "P$4") (pinfunction "BLUE_P$4") (pintype "bidirectional"))
      (node (ref "LED57") (pin "P$4") (pinfunction "BLUE_P$4") (pintype "bidirectional"))
      (node (ref "LED61") (pin "P$4") (pinfunction "BLUE_P$4") (pintype "bidirectional"))
      (node (ref "LED9") (pin "P$4") (pinfunction "BLUE_P$4") (pintype "bidirectional"))
      (node (ref "U1") (pin "6") (pinfunction "OUT2_6") (pintype "bidirectional"))
    )
    (net (code "34") (name "Net-(LED1-GREEN)") (class "Default")
      (node (ref "LED1") (pin "P$3") (pinfunction "GREEN_P$3") (pintype "bidirectional"))
      (node (ref "LED13") (pin "P$3") (pinfunction "GREEN_P$3") (pintype "bidirectional"))
      (node (ref "LED17") (pin "P$3") (pinfunction "GREEN_P$3") (pintype "bidirectional"))
      (node (ref "LED21") (pin "P$3") (pinfunction "GREEN_P$3") (pintype "bidirectional"))
      (node (ref "LED25") (pin "P$3") (pinfunction "GREEN_P$3") (pintype "bidirectional"))
      (node (ref "LED29") (pin "P$3") (pinfunction "GREEN_P$3") (pintype "bidirectional"))
      (node (ref "LED33") (pin "P$3") (pinfunction "GREEN_P$3") (pintype "bidirectional"))
      (node (ref "LED34") (pin "P$3") (pinfunction "GREEN_P$3") (pintype "bidirectional"))
      (node (ref "LED41") (pin "P$3") (pinfunction "GREEN_P$3") (pintype "bidirectional"))
      (node (ref "LED45") (pin "P$3") (pinfunction "GREEN_P$3") (pintype "bidirectional"))
      (node (ref "LED49") (pin "P$3") (pinfunction "GREEN_P$3") (pintype "bidirectional"))
      (node (ref "LED5") (pin "P$3") (pinfunction "GREEN_P$3") (pintype "bidirectional"))
      (node (ref "LED53") (pin "P$3") (pinfunction "GREEN_P$3") (pintype "bidirectional"))
      (node (ref "LED57") (pin "P$3") (pinfunction "GREEN_P$3") (pintype "bidirectional"))
      (node (ref "LED61") (pin "P$3") (pinfunction "GREEN_P$3") (pintype "bidirectional"))
      (node (ref "LED9") (pin "P$3") (pinfunction "GREEN_P$3") (pintype "bidirectional"))
      (node (ref "U1") (pin "5") (pinfunction "OUT1_5") (pintype "bidirectional"))
    )
    (net (code "35") (name "Net-(LED1-RED)") (class "Default")
      (node (ref "LED1") (pin "P$1") (pinfunction "RED_P$1") (pintype "bidirectional"))
      (node (ref "LED13") (pin "P$1") (pinfunction "RED_P$1") (pintype "bidirectional"))
      (node (ref "LED17") (pin "P$1") (pinfunction "RED_P$1") (pintype "bidirectional"))
      (node (ref "LED21") (pin "P$1") (pinfunction "RED_P$1") (pintype "bidirectional"))
      (node (ref "LED25") (pin "P$1") (pinfunction "RED_P$1") (pintype "bidirectional"))
      (node (ref "LED29") (pin "P$1") (pinfunction "RED_P$1") (pintype "bidirectional"))
      (node (ref "LED33") (pin "P$1") (pinfunction "RED_P$1") (pintype "bidirectional"))
      (node (ref "LED34") (pin "P$1") (pinfunction "RED_P$1") (pintype "bidirectional"))
      (node (ref "LED41") (pin "P$1") (pinfunction "RED_P$1") (pintype "bidirectional"))
      (node (ref "LED45") (pin "P$1") (pinfunction "RED_P$1") (pintype "bidirectional"))
      (node (ref "LED49") (pin "P$1") (pinfunction "RED_P$1") (pintype "bidirectional"))
      (node (ref "LED5") (pin "P$1") (pinfunction "RED_P$1") (pintype "bidirectional"))
      (node (ref "LED53") (pin "P$1") (pinfunction "RED_P$1") (pintype "bidirectional"))
      (node (ref "LED57") (pin "P$1") (pinfunction "RED_P$1") (pintype "bidirectional"))
      (node (ref "LED61") (pin "P$1") (pinfunction "RED_P$1") (pintype "bidirectional"))
      (node (ref "LED9") (pin "P$1") (pinfunction "RED_P$1") (pintype "bidirectional"))
      (node (ref "U1") (pin "4") (pinfunction "OUT0_4") (pintype "bidirectional"))
    )
    (net (code "36") (name "Net-(LED1-VCC)") (class "Default")
      (node (ref "LED1") (pin "P$2") (pinfunction "VCC_P$2") (pintype "bidirectional"))
      (node (ref "LED2") (pin "P$2") (pinfunction "VCC_P$2") (pintype "bidirectional"))
      (node (ref "LED3") (pin "P$2") (pinfunction "VCC_P$2") (pintype "bidirectional"))
      (node (ref "LED4") (pin "P$2") (pinfunction "VCC_P$2") (pintype "bidirectional"))
      (node (ref "Q5") (pin "3") (pinfunction "C_3") (pintype "passive"))
    )
    (net (code "37") (name "Net-(LED5-VCC)") (class "Default")
      (node (ref "LED5") (pin "P$2") (pinfunction "VCC_P$2") (pintype "bidirectional"))
      (node (ref "LED6") (pin "P$2") (pinfunction "VCC_P$2") (pintype "bidirectional"))
      (node (ref "LED7") (pin "P$2") (pinfunction "VCC_P$2") (pintype "bidirectional"))
      (node (ref "LED8") (pin "P$2") (pinfunction "VCC_P$2") (pintype "bidirectional"))
      (node (ref "Q6") (pin "3") (pinfunction "C_3") (pintype "passive"))
    )
    (net (code "38") (name "Net-(LED10-BLUE)") (class "Default")
      (node (ref "LED10") (pin "P$4") (pinfunction "BLUE_P$4") (pintype "bidirectional"))
      (node (ref "LED14") (pin "P$4") (pinfunction "BLUE_P$4") (pintype "bidirectional"))
      (node (ref "LED18") (pin "P$4") (pinfunction "BLUE_P$4") (pintype "bidirectional"))
      (node (ref "LED2") (pin "P$4") (pinfunction "BLUE_P$4") (pintype "bidirectional"))
      (node (ref "LED22") (pin "P$4") (pinfunction "BLUE_P$4") (pintype "bidirectional"))
      (node (ref "LED26") (pin "P$4") (pinfunction "BLUE_P$4") (pintype "bidirectional"))
      (node (ref "LED30") (pin "P$4") (pinfunction "BLUE_P$4") (pintype "bidirectional"))
      (node (ref "LED35") (pin "P$4") (pinfunction "BLUE_P$4") (pintype "bidirectional"))
      (node (ref "LED36") (pin "P$4") (pinfunction "BLUE_P$4") (pintype "bidirectional"))
      (node (ref "LED42") (pin "P$4") (pinfunction "BLUE_P$4") (pintype "bidirectional"))
      (node (ref "LED46") (pin "P$4") (pinfunction "BLUE_P$4") (pintype "bidirectional"))
      (node (ref "LED50") (pin "P$4") (pinfunction "BLUE_P$4") (pintype "bidirectional"))
      (node (ref "LED54") (pin "P$4") (pinfunction "BLUE_P$4") (pintype "bidirectional"))
      (node (ref "LED58") (pin "P$4") (pinfunction "BLUE_P$4") (pintype "bidirectional"))
      (node (ref "LED6") (pin "P$4") (pinfunction "BLUE_P$4") (pintype "bidirectional"))
      (node (ref "LED62") (pin "P$4") (pinfunction "BLUE_P$4") (pintype "bidirectional"))
      (node (ref "U1") (pin "9") (pinfunction "OUT5_9") (pintype "bidirectional"))
    )
    (net (code "39") (name "Net-(LED10-GREEN)") (class "Default")
      (node (ref "LED10") (pin "P$3") (pinfunction "GREEN_P$3") (pintype "bidirectional"))
      (node (ref "LED14") (pin "P$3") (pinfunction "GREEN_P$3") (pintype "bidirectional"))
      (node (ref "LED18") (pin "P$3") (pinfunction "GREEN_P$3") (pintype "bidirectional"))
      (node (ref "LED2") (pin "P$3") (pinfunction "GREEN_P$3") (pintype "bidirectional"))
      (node (ref "LED22") (pin "P$3") (pinfunction "GREEN_P$3") (pintype "bidirectional"))
      (node (ref "LED26") (pin "P$3") (pinfunction "GREEN_P$3") (pintype "bidirectional"))
      (node (ref "LED30") (pin "P$3") (pinfunction "GREEN_P$3") (pintype "bidirectional"))
      (node (ref "LED35") (pin "P$3") (pinfunction "GREEN_P$3") (pintype "bidirectional"))
      (node (ref "LED36") (pin "P$3") (pinfunction "GREEN_P$3") (pintype "bidirectional"))
      (node (ref "LED42") (pin "P$3") (pinfunction "GREEN_P$3") (pintype "bidirectional"))
      (node (ref "LED46") (pin "P$3") (pinfunction "GREEN_P$3") (pintype "bidirectional"))
      (node (ref "LED50") (pin "P$3") (pinfunction "GREEN_P$3") (pintype "bidirectional"))
      (node (ref "LED54") (pin "P$3") (pinfunction "GREEN_P$3") (pintype "bidirectional"))
      (node (ref "LED58") (pin "P$3") (pinfunction "GREEN_P$3") (pintype "bidirectional"))
      (node (ref "LED6") (pin "P$3") (pinfunction "GREEN_P$3") (pintype "bidirectional"))
      (node (ref "LED62") (pin "P$3") (pinfunction "GREEN_P$3") (pintype "bidirectional"))
      (node (ref "U1") (pin "8") (pinfunction "OUT4_8") (pintype "bidirectional"))
    )
    (net (code "40") (name "Net-(LED10-RED)") (class "Default")
      (node (ref "LED10") (pin "P$1") (pinfunction "RED_P$1") (pintype "bidirectional"))
      (node (ref "LED14") (pin "P$1") (pinfunction "RED_P$1") (pintype "bidirectional"))
      (node (ref "LED18") (pin "P$1") (pinfunction "RED_P$1") (pintype "bidirectional"))
      (node (ref "LED2") (pin "P$1") (pinfunction "RED_P$1") (pintype "bidirectional"))
      (node (ref "LED22") (pin "P$1") (pinfunction "RED_P$1") (pintype "bidirectional"))
      (node (ref "LED26") (pin "P$1") (pinfunction "RED_P$1") (pintype "bidirectional"))
      (node (ref "LED30") (pin "P$1") (pinfunction "RED_P$1") (pintype "bidirectional"))
      (node (ref "LED35") (pin "P$1") (pinfunction "RED_P$1") (pintype "bidirectional"))
      (node (ref "LED36") (pin "P$1") (pinfunction "RED_P$1") (pintype "bidirectional"))
      (node (ref "LED42") (pin "P$1") (pinfunction "RED_P$1") (pintype "bidirectional"))
      (node (ref "LED46") (pin "P$1") (pinfunction "RED_P$1") (pintype "bidirectional"))
      (node (ref "LED50") (pin "P$1") (pinfunction "RED_P$1") (pintype "bidirectional"))
      (node (ref "LED54") (pin "P$1") (pinfunction "RED_P$1") (pintype "bidirectional"))
      (node (ref "LED58") (pin "P$1") (pinfunction "RED_P$1") (pintype "bidirectional"))
      (node (ref "LED6") (pin "P$1") (pinfunction "RED_P$1") (pintype "bidirectional"))
      (node (ref "LED62") (pin "P$1") (pinfunction "RED_P$1") (pintype "bidirectional"))
      (node (ref "U1") (pin "7") (pinfunction "OUT3_7") (pintype "bidirectional"))
    )
    (net (code "41") (name "Net-(LED10-VCC)") (class "Default")
      (node (ref "LED10") (pin "P$2") (pinfunction "VCC_P$2") (pintype "bidirectional"))
      (node (ref "LED11") (pin "P$2") (pinfunction "VCC_P$2") (pintype "bidirectional"))
      (node (ref "LED12") (pin "P$2") (pinfunction "VCC_P$2") (pintype "bidirectional"))
      (node (ref "LED9") (pin "P$2") (pinfunction "VCC_P$2") (pintype "bidirectional"))
      (node (ref "Q7") (pin "3") (pinfunction "C_3") (pintype "passive"))
    )
    (net (code "42") (name "Net-(LED11-BLUE)") (class "Default")
      (node (ref "LED11") (pin "P$4") (pinfunction "BLUE_P$4") (pintype "bidirectional"))
      (node (ref "LED15") (pin "P$4") (pinfunction "BLUE_P$4") (pintype "bidirectional"))
      (node (ref "LED19") (pin "P$4") (pinfunction "BLUE_P$4") (pintype "bidirectional"))
      (node (ref "LED23") (pin "P$4") (pinfunction "BLUE_P$4") (pintype "bidirectional"))
      (node (ref "LED27") (pin "P$4") (pinfunction "BLUE_P$4") (pintype "bidirectional"))
      (node (ref "LED3") (pin "P$4") (pinfunction "BLUE_P$4") (pintype "bidirectional"))
      (node (ref "LED31") (pin "P$4") (pinfunction "BLUE_P$4") (pintype "bidirectional"))
      (node (ref "LED37") (pin "P$4") (pinfunction "BLUE_P$4") (pintype "bidirectional"))
      (node (ref "LED38") (pin "P$4") (pinfunction "BLUE_P$4") (pintype "bidirectional"))
      (node (ref "LED43") (pin "P$4") (pinfunction "BLUE_P$4") (pintype "bidirectional"))
      (node (ref "LED47") (pin "P$4") (pinfunction "BLUE_P$4") (pintype "bidirectional"))
      (node (ref "LED51") (pin "P$4") (pinfunction "BLUE_P$4") (pintype "bidirectional"))
      (node (ref "LED55") (pin "P$4") (pinfunction "BLUE_P$4") (pintype "bidirectional"))
      (node (ref "LED59") (pin "P$4") (pinfunction "BLUE_P$4") (pintype "bidirectional"))
      (node (ref "LED63") (pin "P$4") (pinfunction "BLUE_P$4") (pintype "bidirectional"))
      (node (ref "LED7") (pin "P$4") (pinfunction "BLUE_P$4") (pintype "bidirectional"))
      (node (ref "U1") (pin "14") (pinfunction "OUT8_14") (pintype "bidirectional"))
    )
    (net (code "43") (name "Net-(LED11-GREEN)") (class "Default")
      (node (ref "LED11") (pin "P$3") (pinfunction "GREEN_P$3") (pintype "bidirectional"))
      (node (ref "LED15") (pin "P$3") (pinfunction "GREEN_P$3") (pintype "bidirectional"))
      (node (ref "LED19") (pin "P$3") (pinfunction "GREEN_P$3") (pintype "bidirectional"))
      (node (ref "LED23") (pin "P$3") (pinfunction "GREEN_P$3") (pintype "bidirectional"))
      (node (ref "LED27") (pin "P$3") (pinfunction "GREEN_P$3") (pintype "bidirectional"))
      (node (ref "LED3") (pin "P$3") (pinfunction "GREEN_P$3") (pintype "bidirectional"))
      (node (ref "LED31") (pin "P$3") (pinfunction "GREEN_P$3") (pintype "bidirectional"))
      (node (ref "LED37") (pin "P$3") (pinfunction "GREEN_P$3") (pintype "bidirectional"))
      (node (ref "LED38") (pin "P$3") (pinfunction "GREEN_P$3") (pintype "bidirectional"))
      (node (ref "LED43") (pin "P$3") (pinfunction "GREEN_P$3") (pintype "bidirectional"))
      (node (ref "LED47") (pin "P$3") (pinfunction "GREEN_P$3") (pintype "bidirectional"))
      (node (ref "LED51") (pin "P$3") (pinfunction "GREEN_P$3") (pintype "bidirectional"))
      (node (ref "LED55") (pin "P$3") (pinfunction "GREEN_P$3") (pintype "bidirectional"))
      (node (ref "LED59") (pin "P$3") (pinfunction "GREEN_P$3") (pintype "bidirectional"))
      (node (ref "LED63") (pin "P$3") (pinfunction "GREEN_P$3") (pintype "bidirectional"))
      (node (ref "LED7") (pin "P$3") (pinfunction "GREEN_P$3") (pintype "bidirectional"))
      (node (ref "U1") (pin "11") (pinfunction "OUT7_11") (pintype "bidirectional"))
    )
    (net (code "44") (name "Net-(LED11-RED)") (class "Default")
      (node (ref "LED11") (pin "P$1") (pinfunction "RED_P$1") (pintype "bidirectional"))
      (node (ref "LED15") (pin "P$1") (pinfunction "RED_P$1") (pintype "bidirectional"))
      (node (ref "LED19") (pin "P$1") (pinfunction "RED_P$1") (pintype "bidirectional"))
      (node (ref "LED23") (pin "P$1") (pinfunction "RED_P$1") (pintype "bidirectional"))
      (node (ref "LED27") (pin "P$1") (pinfunction "RED_P$1") (pintype "bidirectional"))
      (node (ref "LED3") (pin "P$1") (pinfunction "RED_P$1") (pintype "bidirectional"))
      (node (ref "LED31") (pin "P$1") (pinfunction "RED_P$1") (pintype "bidirectional"))
      (node (ref "LED37") (pin "P$1") (pinfunction "RED_P$1") (pintype "bidirectional"))
      (node (ref "LED38") (pin "P$1") (pinfunction "RED_P$1") (pintype "bidirectional"))
      (node (ref "LED43") (pin "P$1") (pinfunction "RED_P$1") (pintype "bidirectional"))
      (node (ref "LED47") (pin "P$1") (pinfunction "RED_P$1") (pintype "bidirectional"))
      (node (ref "LED51") (pin "P$1") (pinfunction "RED_P$1") (pintype "bidirectional"))
      (node (ref "LED55") (pin "P$1") (pinfunction "RED_P$1") (pintype "bidirectional"))
      (node (ref "LED59") (pin "P$1") (pinfunction "RED_P$1") (pintype "bidirectional"))
      (node (ref "LED63") (pin "P$1") (pinfunction "RED_P$1") (pintype "bidirectional"))
      (node (ref "LED7") (pin "P$1") (pinfunction "RED_P$1") (pintype "bidirectional"))
      (node (ref "U1") (pin "10") (pinfunction "OUT6_10") (pintype "bidirectional"))
    )
    (net (code "45") (name "Net-(LED12-BLUE)") (class "Default")
      (node (ref "LED12") (pin "P$4") (pinfunction "BLUE_P$4") (pintype "bidirectional"))
      (node (ref "LED16") (pin "P$4") (pinfunction "BLUE_P$4") (pintype "bidirectional"))
      (node (ref "LED20") (pin "P$4") (pinfunction "BLUE_P$4") (pintype "bidirectional"))
      (node (ref "LED24") (pin "P$4") (pinfunction "BLUE_P$4") (pintype "bidirectional"))
      (node (ref "LED28") (pin "P$4") (pinfunction "BLUE_P$4") (pintype "bidirectional"))
      (node (ref "LED32") (pin "P$4") (pinfunction "BLUE_P$4") (pintype "bidirectional"))
      (node (ref "LED39") (pin "P$4") (pinfunction "BLUE_P$4") (pintype "bidirectional"))
      (node (ref "LED4") (pin "P$4") (pinfunction "BLUE_P$4") (pintype "bidirectional"))
      (node (ref "LED40") (pin "P$4") (pinfunction "BLUE_P$4") (pintype "bidirectional"))
      (node (ref "LED44") (pin "P$4") (pinfunction "BLUE_P$4") (pintype "bidirectional"))
      (node (ref "LED48") (pin "P$4") (pinfunction "BLUE_P$4") (pintype "bidirectional"))
      (node (ref "LED52") (pin "P$4") (pinfunction "BLUE_P$4") (pintype "bidirectional"))
      (node (ref "LED56") (pin "P$4") (pinfunction "BLUE_P$4") (pintype "bidirectional"))
      (node (ref "LED60") (pin "P$4") (pinfunction "BLUE_P$4") (pintype "bidirectional"))
      (node (ref "LED64") (pin "P$4") (pinfunction "BLUE_P$4") (pintype "bidirectional"))
      (node (ref "LED8") (pin "P$4") (pinfunction "BLUE_P$4") (pintype "bidirectional"))
      (node (ref "U1") (pin "17") (pinfunction "OUT11_17") (pintype "bidirectional"))
    )
    (net (code "46") (name "Net-(LED12-GREEN)") (class "Default")
      (node (ref "LED12") (pin "P$3") (pinfunction "GREEN_P$3") (pintype "bidirectional"))
      (node (ref "LED16") (pin "P$3") (pinfunction "GREEN_P$3") (pintype "bidirectional"))
      (node (ref "LED20") (pin "P$3") (pinfunction "GREEN_P$3") (pintype "bidirectional"))
      (node (ref "LED24") (pin "P$3") (pinfunction "GREEN_P$3") (pintype "bidirectional"))
      (node (ref "LED28") (pin "P$3") (pinfunction "GREEN_P$3") (pintype "bidirectional"))
      (node (ref "LED32") (pin "P$3") (pinfunction "GREEN_P$3") (pintype "bidirectional"))
      (node (ref "LED39") (pin "P$3") (pinfunction "GREEN_P$3") (pintype "bidirectional"))
      (node (ref "LED4") (pin "P$3") (pinfunction "GREEN_P$3") (pintype "bidirectional"))
      (node (ref "LED40") (pin "P$3") (pinfunction "GREEN_P$3") (pintype "bidirectional"))
      (node (ref "LED44") (pin "P$3") (pinfunction "GREEN_P$3") (pintype "bidirectional"))
      (node (ref "LED48") (pin "P$3") (pinfunction "GREEN_P$3") (pintype "bidirectional"))
      (node (ref "LED52") (pin "P$3") (pinfunction "GREEN_P$3") (pintype "bidirectional"))
      (node (ref "LED56") (pin "P$3") (pinfunction "GREEN_P$3") (pintype "bidirectional"))
      (node (ref "LED60") (pin "P$3") (pinfunction "GREEN_P$3") (pintype "bidirectional"))
      (node (ref "LED64") (pin "P$3") (pinfunction "GREEN_P$3") (pintype "bidirectional"))
      (node (ref "LED8") (pin "P$3") (pinfunction "GREEN_P$3") (pintype "bidirectional"))
      (node (ref "U1") (pin "16") (pinfunction "OUT10_16") (pintype "bidirectional"))
    )
    (net (code "47") (name "Net-(LED12-RED)") (class "Default")
      (node (ref "LED12") (pin "P$1") (pinfunction "RED_P$1") (pintype "bidirectional"))
      (node (ref "LED16") (pin "P$1") (pinfunction "RED_P$1") (pintype "bidirectional"))
      (node (ref "LED20") (pin "P$1") (pinfunction "RED_P$1") (pintype "bidirectional"))
      (node (ref "LED24") (pin "P$1") (pinfunction "RED_P$1") (pintype "bidirectional"))
      (node (ref "LED28") (pin "P$1") (pinfunction "RED_P$1") (pintype "bidirectional"))
      (node (ref "LED32") (pin "P$1") (pinfunction "RED_P$1") (pintype "bidirectional"))
      (node (ref "LED39") (pin "P$1") (pinfunction "RED_P$1") (pintype "bidirectional"))
      (node (ref "LED4") (pin "P$1") (pinfunction "RED_P$1") (pintype "bidirectional"))
      (node (ref "LED40") (pin "P$1") (pinfunction "RED_P$1") (pintype "bidirectional"))
      (node (ref "LED44") (pin "P$1") (pinfunction "RED_P$1") (pintype "bidirectional"))
      (node (ref "LED48") (pin "P$1") (pinfunction "RED_P$1") (pintype "bidirectional"))
      (node (ref "LED52") (pin "P$1") (pinfunction "RED_P$1") (pintype "bidirectional"))
      (node (ref "LED56") (pin "P$1") (pinfunction "RED_P$1") (pintype "bidirectional"))
      (node (ref "LED60") (pin "P$1") (pinfunction "RED_P$1") (pintype "bidirectional"))
      (node (ref "LED64") (pin "P$1") (pinfunction "RED_P$1") (pintype "bidirectional"))
      (node (ref "LED8") (pin "P$1") (pinfunction "RED_P$1") (pintype "bidirectional"))
      (node (ref "U1") (pin "15") (pinfunction "OUT9_15") (pintype "bidirectional"))
    )
    (net (code "48") (name "Net-(LED13-VCC)") (class "Default")
      (node (ref "LED13") (pin "P$2") (pinfunction "VCC_P$2") (pintype "bidirectional"))
      (node (ref "LED14") (pin "P$2") (pinfunction "VCC_P$2") (pintype "bidirectional"))
      (node (ref "LED15") (pin "P$2") (pinfunction "VCC_P$2") (pintype "bidirectional"))
      (node (ref "LED16") (pin "P$2") (pinfunction "VCC_P$2") (pintype "bidirectional"))
      (node (ref "Q8") (pin "3") (pinfunction "C_3") (pintype "passive"))
    )
    (net (code "49") (name "Net-(LED17-VCC)") (class "Default")
      (node (ref "LED17") (pin "P$2") (pinfunction "VCC_P$2") (pintype "bidirectional"))
      (node (ref "LED18") (pin "P$2") (pinfunction "VCC_P$2") (pintype "bidirectional"))
      (node (ref "LED19") (pin "P$2") (pinfunction "VCC_P$2") (pintype "bidirectional"))
      (node (ref "LED20") (pin "P$2") (pinfunction "VCC_P$2") (pintype "bidirectional"))
      (node (ref "Q1") (pin "3") (pinfunction "C_3") (pintype "passive"))
    )
    (net (code "50") (name "Net-(LED21-VCC)") (class "Default")
      (node (ref "LED21") (pin "P$2") (pinfunction "VCC_P$2") (pintype "bidirectional"))
      (node (ref "LED22") (pin "P$2") (pinfunction "VCC_P$2") (pintype "bidirectional"))
      (node (ref "LED23") (pin "P$2") (pinfunction "VCC_P$2") (pintype "bidirectional"))
      (node (ref "LED24") (pin "P$2") (pinfunction "VCC_P$2") (pintype "bidirectional"))
      (node (ref "Q2") (pin "3") (pinfunction "C_3") (pintype "passive"))
    )
    (net (code "51") (name "Net-(LED25-VCC)") (class "Default")
      (node (ref "LED25") (pin "P$2") (pinfunction "VCC_P$2") (pintype "bidirectional"))
      (node (ref "LED26") (pin "P$2") (pinfunction "VCC_P$2") (pintype "bidirectional"))
      (node (ref "LED27") (pin "P$2") (pinfunction "VCC_P$2") (pintype "bidirectional"))
      (node (ref "LED28") (pin "P$2") (pinfunction "VCC_P$2") (pintype "bidirectional"))
      (node (ref "Q3") (pin "3") (pinfunction "C_3") (pintype "passive"))
    )
    (net (code "52") (name "Net-(LED29-VCC)") (class "Default")
      (node (ref "LED29") (pin "P$2") (pinfunction "VCC_P$2") (pintype "bidirectional"))
      (node (ref "LED30") (pin "P$2") (pinfunction "VCC_P$2") (pintype "bidirectional"))
      (node (ref "LED31") (pin "P$2") (pinfunction "VCC_P$2") (pintype "bidirectional"))
      (node (ref "LED32") (pin "P$2") (pinfunction "VCC_P$2") (pintype "bidirectional"))
      (node (ref "Q4") (pin "3") (pinfunction "C_3") (pintype "passive"))
    )
    (net (code "53") (name "Net-(LED33-VCC)") (class "Default")
      (node (ref "LED33") (pin "P$2") (pinfunction "VCC_P$2") (pintype "bidirectional"))
      (node (ref "LED35") (pin "P$2") (pinfunction "VCC_P$2") (pintype "bidirectional"))
      (node (ref "LED37") (pin "P$2") (pinfunction "VCC_P$2") (pintype "bidirectional"))
      (node (ref "LED39") (pin "P$2") (pinfunction "VCC_P$2") (pintype "bidirectional"))
      (node (ref "Q13") (pin "3") (pinfunction "C_3") (pintype "passive"))
    )
    (net (code "54") (name "Net-(LED34-VCC)") (class "Default")
      (node (ref "LED34") (pin "P$2") (pinfunction "VCC_P$2") (pintype "bidirectional"))
      (node (ref "LED36") (pin "P$2") (pinfunction "VCC_P$2") (pintype "bidirectional"))
      (node (ref "LED38") (pin "P$2") (pinfunction "VCC_P$2") (pintype "bidirectional"))
      (node (ref "LED40") (pin "P$2") (pinfunction "VCC_P$2") (pintype "bidirectional"))
      (node (ref "Q14") (pin "3") (pinfunction "C_3") (pintype "passive"))
    )
    (net (code "55") (name "Net-(LED41-VCC)") (class "Default")
      (node (ref "LED41") (pin "P$2") (pinfunction "VCC_P$2") (pintype "bidirectional"))
      (node (ref "LED42") (pin "P$2") (pinfunction "VCC_P$2") (pintype "bidirectional"))
      (node (ref "LED43") (pin "P$2") (pinfunction "VCC_P$2") (pintype "bidirectional"))
      (node (ref "LED44") (pin "P$2") (pinfunction "VCC_P$2") (pintype "bidirectional"))
      (node (ref "Q15") (pin "3") (pinfunction "C_3") (pintype "passive"))
    )
    (net (code "56") (name "Net-(LED45-VCC)") (class "Default")
      (node (ref "LED45") (pin "P$2") (pinfunction "VCC_P$2") (pintype "bidirectional"))
      (node (ref "LED46") (pin "P$2") (pinfunction "VCC_P$2") (pintype "bidirectional"))
      (node (ref "LED47") (pin "P$2") (pinfunction "VCC_P$2") (pintype "bidirectional"))
      (node (ref "LED48") (pin "P$2") (pinfunction "VCC_P$2") (pintype "bidirectional"))
      (node (ref "Q16") (pin "3") (pinfunction "C_3") (pintype "passive"))
    )
    (net (code "57") (name "Net-(LED49-VCC)") (class "Default")
      (node (ref "LED49") (pin "P$2") (pinfunction "VCC_P$2") (pintype "bidirectional"))
      (node (ref "LED50") (pin "P$2") (pinfunction "VCC_P$2") (pintype "bidirectional"))
      (node (ref "LED51") (pin "P$2") (pinfunction "VCC_P$2") (pintype "bidirectional"))
      (node (ref "LED52") (pin "P$2") (pinfunction "VCC_P$2") (pintype "bidirectional"))
      (node (ref "Q9") (pin "3") (pinfunction "C_3") (pintype "passive"))
    )
    (net (code "58") (name "Net-(LED53-VCC)") (class "Default")
      (node (ref "LED53") (pin "P$2") (pinfunction "VCC_P$2") (pintype "bidirectional"))
      (node (ref "LED54") (pin "P$2") (pinfunction "VCC_P$2") (pintype "bidirectional"))
      (node (ref "LED55") (pin "P$2") (pinfunction "VCC_P$2") (pintype "bidirectional"))
      (node (ref "LED56") (pin "P$2") (pinfunction "VCC_P$2") (pintype "bidirectional"))
      (node (ref "Q10") (pin "3") (pinfunction "C_3") (pintype "passive"))
    )
    (net (code "59") (name "Net-(LED57-VCC)") (class "Default")
      (node (ref "LED57") (pin "P$2") (pinfunction "VCC_P$2") (pintype "bidirectional"))
      (node (ref "LED58") (pin "P$2") (pinfunction "VCC_P$2") (pintype "bidirectional"))
      (node (ref "LED59") (pin "P$2") (pinfunction "VCC_P$2") (pintype "bidirectional"))
      (node (ref "LED60") (pin "P$2") (pinfunction "VCC_P$2") (pintype "bidirectional"))
      (node (ref "Q11") (pin "3") (pinfunction "C_3") (pintype "passive"))
    )
    (net (code "60") (name "Net-(LED61-VCC)") (class "Default")
      (node (ref "LED61") (pin "P$2") (pinfunction "VCC_P$2") (pintype "bidirectional"))
      (node (ref "LED62") (pin "P$2") (pinfunction "VCC_P$2") (pintype "bidirectional"))
      (node (ref "LED63") (pin "P$2") (pinfunction "VCC_P$2") (pintype "bidirectional"))
      (node (ref "LED64") (pin "P$2") (pinfunction "VCC_P$2") (pintype "bidirectional"))
      (node (ref "Q12") (pin "3") (pinfunction "C_3") (pintype "passive"))
    )
    (net (code "61") (name "Net-(Q1-B)") (class "Default")
      (node (ref "Q1") (pin "2") (pinfunction "B_2") (pintype "passive"))
      (node (ref "R1") (pin "2") (pinfunction "2_2") (pintype "passive"))
      (node (ref "R2") (pin "1") (pinfunction "1_1") (pintype "passive"))
    )
    (net (code "62") (name "Net-(Q1-E)") (class "Default")
      (node (ref "Q1") (pin "1") (pinfunction "E_1") (pintype "passive"))
      (node (ref "Q10") (pin "1") (pinfunction "E_1") (pintype "passive"))
      (node (ref "Q11") (pin "1") (pinfunction "E_1") (pintype "passive"))
      (node (ref "Q12") (pin "1") (pinfunction "E_1") (pintype "passive"))
      (node (ref "Q13") (pin "1") (pinfunction "E_1") (pintype "passive"))
      (node (ref "Q14") (pin "1") (pinfunction "E_1") (pintype "passive"))
      (node (ref "Q15") (pin "1") (pinfunction "E_1") (pintype "passive"))
      (node (ref "Q16") (pin "1") (pinfunction "E_1") (pintype "passive"))
      (node (ref "Q2") (pin "1") (pinfunction "E_1") (pintype "passive"))
      (node (ref "Q3") (pin "1") (pinfunction "E_1") (pintype "passive"))
      (node (ref "Q4") (pin "1") (pinfunction "E_1") (pintype "passive"))
      (node (ref "Q5") (pin "1") (pinfunction "E_1") (pintype "passive"))
      (node (ref "Q6") (pin "1") (pinfunction "E_1") (pintype "passive"))
      (node (ref "Q7") (pin "1") (pinfunction "E_1") (pintype "passive"))
      (node (ref "Q8") (pin "1") (pinfunction "E_1") (pintype "passive"))
      (node (ref "Q9") (pin "1") (pinfunction "E_1") (pintype "passive"))
      (node (ref "R10") (pin "2") (pinfunction "2_2") (pintype "passive"))
      (node (ref "R12") (pin "2") (pinfunction "2_2") (pintype "passive"))
      (node (ref "R14") (pin "2") (pinfunction "2_2") (pintype "passive"))
      (node (ref "R16") (pin "2") (pinfunction "2_2") (pintype "passive"))
      (node (ref "R18") (pin "2") (pinfunction "2_2") (pintype "passive"))
      (node (ref "R2") (pin "2") (pinfunction "2_2") (pintype "passive"))
      (node (ref "R20") (pin "2") (pinfunction "2_2") (pintype "passive"))
      (node (ref "R22") (pin "2") (pinfunction "2_2") (pintype "passive"))
      (node (ref "R24") (pin "2") (pinfunction "2_2") (pintype "passive"))
      (node (ref "R26") (pin "2") (pinfunction "2_2") (pintype "passive"))
      (node (ref "R28") (pin "2") (pinfunction "2_2") (pintype "passive"))
      (node (ref "R30") (pin "2") (pinfunction "2_2") (pintype "passive"))
      (node (ref "R32") (pin "2") (pinfunction "2_2") (pintype "passive"))
      (node (ref "R4") (pin "2") (pinfunction "2_2") (pintype "passive"))
      (node (ref "R6") (pin "2") (pinfunction "2_2") (pintype "passive"))
      (node (ref "R8") (pin "2") (pinfunction "2_2") (pintype "passive"))
    )
    (net (code "63") (name "Net-(Q2-B)") (class "Default")
      (node (ref "Q2") (pin "2") (pinfunction "B_2") (pintype "passive"))
      (node (ref "R3") (pin "2") (pinfunction "2_2") (pintype "passive"))
      (node (ref "R4") (pin "1") (pinfunction "1_1") (pintype "passive"))
    )
    (net (code "64") (name "Net-(Q3-B)") (class "Default")
      (node (ref "Q3") (pin "2") (pinfunction "B_2") (pintype "passive"))
      (node (ref "R5") (pin "2") (pinfunction "2_2") (pintype "passive"))
      (node (ref "R6") (pin "1") (pinfunction "1_1") (pintype "passive"))
    )
    (net (code "65") (name "Net-(Q4-B)") (class "Default")
      (node (ref "Q4") (pin "2") (pinfunction "B_2") (pintype "passive"))
      (node (ref "R7") (pin "2") (pinfunction "2_2") (pintype "passive"))
      (node (ref "R8") (pin "1") (pinfunction "1_1") (pintype "passive"))
    )
    (net (code "66") (name "Net-(Q5-B)") (class "Default")
      (node (ref "Q5") (pin "2") (pinfunction "B_2") (pintype "passive"))
      (node (ref "R10") (pin "1") (pinfunction "1_1") (pintype "passive"))
      (node (ref "R9") (pin "2") (pinfunction "2_2") (pintype "passive"))
    )
    (net (code "67") (name "Net-(Q6-B)") (class "Default")
      (node (ref "Q6") (pin "2") (pinfunction "B_2") (pintype "passive"))
      (node (ref "R11") (pin "2") (pinfunction "2_2") (pintype "passive"))
      (node (ref "R12") (pin "1") (pinfunction "1_1") (pintype "passive"))
    )
    (net (code "68") (name "Net-(Q7-B)") (class "Default")
      (node (ref "Q7") (pin "2") (pinfunction "B_2") (pintype "passive"))
      (node (ref "R13") (pin "2") (pinfunction "2_2") (pintype "passive"))
      (node (ref "R14") (pin "1") (pinfunction "1_1") (pintype "passive"))
    )
    (net (code "69") (name "Net-(Q8-B)") (class "Default")
      (node (ref "Q8") (pin "2") (pinfunction "B_2") (pintype "passive"))
      (node (ref "R15") (pin "2") (pinfunction "2_2") (pintype "passive"))
      (node (ref "R16") (pin "1") (pinfunction "1_1") (pintype "passive"))
    )
    (net (code "70") (name "Net-(Q9-B)") (class "Default")
      (node (ref "Q9") (pin "2") (pinfunction "B_2") (pintype "passive"))
      (node (ref "R17") (pin "2") (pinfunction "2_2") (pintype "passive"))
      (node (ref "R18") (pin "1") (pinfunction "1_1") (pintype "passive"))
    )
    (net (code "71") (name "Net-(Q10-B)") (class "Default")
      (node (ref "Q10") (pin "2") (pinfunction "B_2") (pintype "passive"))
      (node (ref "R19") (pin "2") (pinfunction "2_2") (pintype "passive"))
      (node (ref "R20") (pin "1") (pinfunction "1_1") (pintype "passive"))
    )
    (net (code "72") (name "Net-(Q11-B)") (class "Default")
      (node (ref "Q11") (pin "2") (pinfunction "B_2") (pintype "passive"))
      (node (ref "R21") (pin "2") (pinfunction "2_2") (pintype "passive"))
      (node (ref "R22") (pin "1") (pinfunction "1_1") (pintype "passive"))
    )
    (net (code "73") (name "Net-(Q12-B)") (class "Default")
      (node (ref "Q12") (pin "2") (pinfunction "B_2") (pintype "passive"))
      (node (ref "R23") (pin "2") (pinfunction "2_2") (pintype "passive"))
      (node (ref "R24") (pin "1") (pinfunction "1_1") (pintype "passive"))
    )
    (net (code "74") (name "Net-(Q13-B)") (class "Default")
      (node (ref "Q13") (pin "2") (pinfunction "B_2") (pintype "passive"))
      (node (ref "R25") (pin "2") (pinfunction "2_2") (pintype "passive"))
      (node (ref "R26") (pin "1") (pinfunction "1_1") (pintype "passive"))
    )
    (net (code "75") (name "Net-(Q14-B)") (class "Default")
      (node (ref "Q14") (pin "2") (pinfunction "B_2") (pintype "passive"))
      (node (ref "R27") (pin "2") (pinfunction "2_2") (pintype "passive"))
      (node (ref "R28") (pin "1") (pinfunction "1_1") (pintype "passive"))
    )
    (net (code "76") (name "Net-(Q15-B)") (class "Default")
      (node (ref "Q15") (pin "2") (pinfunction "B_2") (pintype "passive"))
      (node (ref "R29") (pin "2") (pinfunction "2_2") (pintype "passive"))
      (node (ref "R30") (pin "1") (pinfunction "1_1") (pintype "passive"))
    )
    (net (code "77") (name "Net-(Q16-B)") (class "Default")
      (node (ref "Q16") (pin "2") (pinfunction "B_2") (pintype "passive"))
      (node (ref "R31") (pin "2") (pinfunction "2_2") (pintype "passive"))
      (node (ref "R32") (pin "1") (pinfunction "1_1") (pintype "passive"))
    )
    (net (code "78") (name "Net-(S1-P)") (class "Default")
      (node (ref "J1") (pin "2") (pinfunction "2_2") (pintype "passive"))
      (node (ref "J1") (pin "3") (pinfunction "3_3") (pintype "passive"))
      (node (ref "S1") (pin "2") (pinfunction "P_2") (pintype "passive"))
    )
    (net (code "79") (name "Net-(U1-DCPRG)") (class "Default")
      (node (ref "R37") (pin "1") (pinfunction "1_1") (pintype "passive"))
      (node (ref "U1") (pin "25") (pinfunction "DCPRG_25") (pintype "bidirectional"))
    )
    (net (code "80") (name "Net-(U1-GSCLK)") (class "Default")
      (node (ref "R35") (pin "1") (pinfunction "1_1") (pintype "passive"))
      (node (ref "U1") (pin "24") (pinfunction "GSCLK_24") (pintype "bidirectional"))
    )
    (net (code "81") (name "Net-(U1-IREF)") (class "Default")
      (node (ref "R34") (pin "2") (pinfunction "2_2") (pintype "passive"))
      (node (ref "U1") (pin "26") (pinfunction "IREF_26") (pintype "bidirectional"))
    )
    (net (code "82") (name "unconnected-(IC2-PC0(ADC0{slash}PCINT8)-Pad23)") (class "Default")
      (node (ref "IC2") (pin "23") (pinfunction "PC0(ADC0/PCINT8)_23") (pintype "bidirectional"))
    )
    (net (code "83") (name "unconnected-(IC2-PC1(ADC1{slash}PCINT9)-Pad24)") (class "Default")
      (node (ref "IC2") (pin "24") (pinfunction "PC1(ADC1/PCINT9)_24") (pintype "bidirectional"))
    )
    (net (code "84") (name "unconnected-(IC2-PC2(ADC2{slash}PCINT10)-Pad25)") (class "Default")
      (node (ref "IC2") (pin "25") (pinfunction "PC2(ADC2/PCINT10)_25") (pintype "bidirectional"))
    )
    (net (code "85") (name "unconnected-(IC2-PC3(ADC3{slash}PCINT11)-Pad26)") (class "Default")
      (node (ref "IC2") (pin "26") (pinfunction "PC3(ADC3/PCINT11)_26") (pintype "bidirectional"))
    )
    (net (code "86") (name "unconnected-(IC2-PC4(ADC4{slash}SDA{slash}PCINT12)-Pad27)") (class "Default")
      (node (ref "IC2") (pin "27") (pinfunction "PC4(ADC4/SDA/PCINT12)_27") (pintype "bidirectional"))
    )
    (net (code "87") (name "unconnected-(IC2-PC5(ADC5{slash}SCLPCINT13)-Pad28)") (class "Default")
      (node (ref "IC2") (pin "28") (pinfunction "PC5(ADC5/SCLPCINT13)_28") (pintype "bidirectional"))
    )
    (net (code "88") (name "unconnected-(IC2-PC6({slash}RESET{slash}PCINT14)-Pad1)") (class "Default")
      (node (ref "IC2") (pin "1") (pinfunction "PC6(/RESET/PCINT14)_1") (pintype "bidirectional"))
    )
    (net (code "89") (name "unconnected-(IC2-PD0(RXD{slash}PCINT16)-Pad2)") (class "Default")
      (node (ref "IC2") (pin "2") (pinfunction "PD0(RXD/PCINT16)_2") (pintype "bidirectional"))
    )
    (net (code "90") (name "unconnected-(IC2-PD1(TXD{slash}PCINT17)-Pad3)") (class "Default")
      (node (ref "IC2") (pin "3") (pinfunction "PD1(TXD/PCINT17)_3") (pintype "bidirectional"))
    )
    (net (code "91") (name "unconnected-(IC2-PD2(INT0{slash}PCINT18)-Pad4)") (class "Default")
      (node (ref "IC2") (pin "4") (pinfunction "PD2(INT0/PCINT18)_4") (pintype "bidirectional"))
    )
    (net (code "92") (name "unconnected-(IC2-PD4(T0{slash}XCK{slash}PCINT20)-Pad6)") (class "Default")
      (node (ref "IC2") (pin "6") (pinfunction "PD4(T0/XCK/PCINT20)_6") (pintype "bidirectional"))
    )
    (net (code "93") (name "unconnected-(IC2-PD5(T1{slash}OC0B{slash}PCINT21)-Pad11)") (class "Default")
      (node (ref "IC2") (pin "11") (pinfunction "PD5(T1/OC0B/PCINT21)_11") (pintype "bidirectional"))
    )
    (net (code "94") (name "unconnected-(IC2-PD7(AIN1{slash}PCINT23)-Pad13)") (class "Default")
      (node (ref "IC2") (pin "13") (pinfunction "PD7(AIN1/PCINT23)_13") (pintype "bidirectional"))
    )
    (net (code "95") (name "unconnected-(S1-O-Pad1)") (class "Default")
      (node (ref "S1") (pin "1") (pinfunction "O_1") (pintype "passive"))
    )
    (net (code "96") (name "unconnected-(U1-OUT12-Pad18)") (class "Default")
      (node (ref "U1") (pin "18") (pinfunction "OUT12_18") (pintype "bidirectional"))
    )
    (net (code "97") (name "unconnected-(U1-OUT13-Pad19)") (class "Default")
      (node (ref "U1") (pin "19") (pinfunction "OUT13_19") (pintype "bidirectional"))
    )
    (net (code "98") (name "unconnected-(U1-OUT14-Pad20)") (class "Default")
      (node (ref "U1") (pin "20") (pinfunction "OUT14_20") (pintype "bidirectional"))
    )
    (net (code "99") (name "unconnected-(U1-OUT15-Pad21)") (class "Default")
      (node (ref "U1") (pin "21") (pinfunction "OUT15_21") (pintype "bidirectional"))
    )
    (net (code "100") (name "unconnected-(U1-XERR-Pad22)") (class "Default")
      (node (ref "U1") (pin "22") (pinfunction "XERR_22") (pintype "bidirectional"))
    )
  )
)
